# microscope_pcb.net
KiCad netlist of a schematic drawn in EAGLE
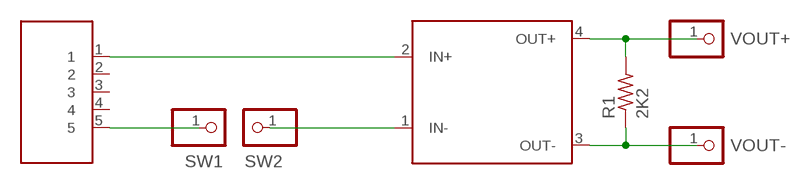
[diagram p0: schematic, sheet 1]

(export (version "E")
  (design (tool "Eeschema 10.0.6"))
  (components
    (comp (ref "R1")
      (value "2K2")
      (footprint "eagle-import:R0805")
      (libsource (lib "eagle-import") (part "R-US_R0805"))
    )
    (comp (ref "SW1")
      (value "PINHD-1X1")
      (footprint "eagle-import:1X01")
      (libsource (lib "eagle-import") (part "PINHD-1X1"))
    )
    (comp (ref "SW2")
      (value "PINHD-1X1")
      (footprint "eagle-import:1X01")
      (libsource (lib "eagle-import") (part "PINHD-1X1"))
    )
    (comp (ref "U$1")
      (value "DC_DC")
      (footprint "eagle-import:DC_DC")
      (libsource (lib "eagle-import") (part "DC_DC"))
    )
    (comp (ref "U$2")
      (value "USB_CONNECTOR")
      (footprint "eagle-import:USB_CONNECTOR")
      (libsource (lib "eagle-import") (part "USB_CONNECTOR"))
    )
    (comp (ref "VOUT+")
      (value "PINHD-1X1")
      (footprint "eagle-import:1X01")
      (libsource (lib "eagle-import") (part "PINHD-1X1"))
    )
    (comp (ref "VOUT-")
      (value "PINHD-1X1")
      (footprint "eagle-import:1X01")
      (libsource (lib "eagle-import") (part "PINHD-1X1"))
    )
  )
  (nets
    (net (code "1") (name "Net-(SW1-Pad1)") (class "Default")
      (node (ref "SW1") (pin "1") (pinfunction "1_1") (pintype "passive"))
      (node (ref "U$2") (pin "5") (pinfunction "5_5") (pintype "bidirectional"))
    )
    (net (code "2") (name "Net-(U$1-IN+)") (class "Default")
      (node (ref "U$1") (pin "2") (pinfunction "IN+_2") (pintype "bidirectional"))
      (node (ref "U$2") (pin "1") (pinfunction "1_1") (pintype "bidirectional"))
    )
    (net (code "3") (name "Net-(U$1-IN-)") (class "Default")
      (node (ref "SW2") (pin "1") (pinfunction "1_1") (pintype "passive"))
      (node (ref "U$1") (pin "1") (pinfunction "IN-_1") (pintype "bidirectional"))
    )
    (net (code "4") (name "Net-(U$1-OUT+)") (class "Default")
      (node (ref "R1") (pin "2") (pinfunction "2_2") (pintype "passive"))
      (node (ref "U$1") (pin "4") (pinfunction "OUT+_4") (pintype "bidirectional"))
      (node (ref "VOUT+") (pin "1") (pinfunction "1_1") (pintype "passive"))
    )
    (net (code "5") (name "Net-(U$1-OUT-)") (class "Default")
      (node (ref "R1") (pin "1") (pinfunction "1_1") (pintype "passive"))
      (node (ref "U$1") (pin "3") (pinfunction "OUT-_3") (pintype "bidirectional"))
      (node (ref "VOUT-") (pin "1") (pinfunction "1_1") (pintype "passive"))
    )
    (net (code "6") (name "unconnected-(U$2-Pad2)") (class "Default")
      (node (ref "U$2") (pin "2") (pinfunction "2_2") (pintype "bidirectional"))
    )
    (net (code "7") (name "unconnected-(U$2-Pad3)") (class "Default")
      (node (ref "U$2") (pin "3") (pinfunction "3_3") (pintype "bidirectional"))
    )
    (net (code "8") (name "unconnected-(U$2-Pad4)") (class "Default")
      (node (ref "U$2") (pin "4") (pinfunction "4_4") (pintype "bidirectional"))
    )
  )
)
